# OPA847.net
KiCad netlist of a schematic drawn in Altium Designer
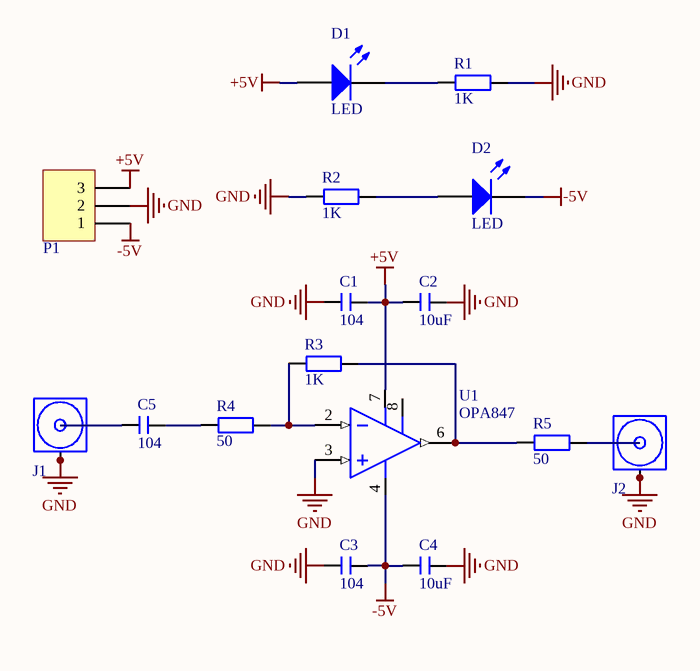
[diagram p0: OPA847.SchDoc]

(export (version "E")
  (design (tool "Eeschema 10.0.6"))
  (components
    (comp (ref "C1")
      (value "104")
      (footprint "C 0805")
      (description "无极性贴片电容")
      (fields (field (name "版权归属") "源创客"))
      (libsource (lib "电阻-电容-电感") (part "C"))
    )
    (comp (ref "C2")
      (value "10uF")
      (footprint "C 0805")
      (description "无极性贴片电容")
      (fields (field (name "版权归属") "源创客"))
      (libsource (lib "电阻-电容-电感") (part "C"))
    )
    (comp (ref "C3")
      (value "104")
      (footprint "C 0805")
      (description "无极性贴片电容")
      (fields (field (name "版权归属") "源创客"))
      (libsource (lib "电阻-电容-电感") (part "C"))
    )
    (comp (ref "C4")
      (value "10uF")
      (footprint "C 0805")
      (description "无极性贴片电容")
      (fields (field (name "版权归属") "源创客"))
      (libsource (lib "电阻-电容-电感") (part "C"))
    )
    (comp (ref "C5")
      (value "104")
      (footprint "C 0603")
      (description "无极性贴片电容")
      (fields (field (name "版权归属") "源创客"))
      (libsource (lib "电阻-电容-电感") (part "C"))
    )
    (comp (ref "D1")
      (value "LED")
      (footprint "LED_0805")
      (description "发光二极管")
      (fields (field (name "PUBLISHER") "Altium Limited"))
      (libsource (lib "LIB") (part "LED"))
    )
    (comp (ref "D2")
      (value "LED")
      (footprint "LED_0805")
      (description "发光二极管")
      (fields (field (name "PUBLISHER") "Altium Limited"))
      (libsource (lib "LIB") (part "LED"))
    )
    (comp (ref "J1") (value "COAX") (footprint "MCX5.08-5-H") (libsource (lib "LIB") (part "COAX")))
    (comp (ref "J2") (value "COAX") (footprint "MCX5.08-5-H") (libsource (lib "LIB") (part "COAX")))
    (comp (ref "P1")
      (value "Header 3")
      (footprint "HDR3X1_B2")
      (description "接插件")
      (fields (field (name "PUBLISHER") "Altium Limited"))
      (libsource (lib "LIB") (part "Header 3"))
    )
    (comp (ref "R1")
      (value "1K")
      (footprint "R 0805")
      (description "贴片电阻")
      (fields (field (name "版权归属") "源创客"))
      (libsource (lib "电阻-电容-电感") (part "R"))
    )
    (comp (ref "R2")
      (value "1K")
      (footprint "R 0805")
      (description "贴片电阻")
      (fields (field (name "版权归属") "源创客"))
      (libsource (lib "电阻-电容-电感") (part "R"))
    )
    (comp (ref "R3")
      (value "1K")
      (footprint "R 0603")
      (description "贴片电阻")
      (fields (field (name "版权归属") "源创客"))
      (libsource (lib "电阻-电容-电感") (part "R"))
    )
    (comp (ref "R4")
      (value "50")
      (footprint "R 0603")
      (description "贴片电阻")
      (fields (field (name "版权归属") "源创客"))
      (libsource (lib "电阻-电容-电感") (part "R"))
    )
    (comp (ref "R5")
      (value "50")
      (footprint "R 0603")
      (description "贴片电阻")
      (fields (field (name "版权归属") "源创客"))
      (libsource (lib "电阻-电容-电感") (part "R"))
    )
    (comp (ref "U1")
      (value "OPA847")
      (footprint "SO8_N")
      (description "Wideband, Ultra-Low Noise, Voltage-Feedback")
      (libsource (lib "LIB") (part "OPA847"))
    )
  )
  (nets
    (net (code "1") (name "+5V") (class "Default")
      (node (ref "C1") (pin "2") (pinfunction "2_2") (pintype "passive"))
      (node (ref "C2") (pin "1") (pinfunction "1_1") (pintype "passive"))
      (node (ref "D1") (pin "1") (pinfunction "A_1") (pintype "passive"))
      (node (ref "P1") (pin "3") (pinfunction "3_3") (pintype "passive"))
      (node (ref "U1") (pin "7") (pinfunction "V+_7") (pintype "power_in"))
    )
    (net (code "2") (name "-5V") (class "Default")
      (node (ref "C3") (pin "2") (pinfunction "2_2") (pintype "passive"))
      (node (ref "C4") (pin "1") (pinfunction "1_1") (pintype "passive"))
      (node (ref "D2") (pin "2") (pinfunction "K_2") (pintype "passive"))
      (node (ref "P1") (pin "1") (pinfunction "1_1") (pintype "passive"))
      (node (ref "U1") (pin "4") (pinfunction "V-_4") (pintype "power_in"))
    )
    (net (code "3") (name "GND") (class "Default")
      (node (ref "C1") (pin "1") (pinfunction "1_1") (pintype "passive"))
      (node (ref "C2") (pin "2") (pinfunction "2_2") (pintype "passive"))
      (node (ref "C3") (pin "1") (pinfunction "1_1") (pintype "passive"))
      (node (ref "C4") (pin "2") (pinfunction "2_2") (pintype "passive"))
      (node (ref "J1") (pin "2") (pinfunction "GND_2") (pintype "passive"))
      (node (ref "J1") (pin "3") (pinfunction "GND_3") (pintype "passive"))
      (node (ref "J1") (pin "4") (pinfunction "GND_4") (pintype "passive"))
      (node (ref "J1") (pin "5") (pinfunction "GND_5") (pintype "passive"))
      (node (ref "J2") (pin "2") (pinfunction "GND_2") (pintype "passive"))
      (node (ref "J2") (pin "3") (pinfunction "GND_3") (pintype "passive"))
      (node (ref "J2") (pin "4") (pinfunction "GND_4") (pintype "passive"))
      (node (ref "J2") (pin "5") (pinfunction "GND_5") (pintype "passive"))
      (node (ref "P1") (pin "2") (pinfunction "2_2") (pintype "passive"))
      (node (ref "R1") (pin "2") (pinfunction "2_2") (pintype "passive"))
      (node (ref "R2") (pin "1") (pinfunction "1_1") (pintype "passive"))
      (node (ref "U1") (pin "3") (pinfunction "IN+_3") (pintype "input"))
    )
    (net (code "4") (name "Net-(C5-Pad2)") (class "Default")
      (node (ref "C5") (pin "2") (pinfunction "2_2") (pintype "passive"))
      (node (ref "R4") (pin "1") (pinfunction "1_1") (pintype "passive"))
    )
    (net (code "5") (name "Net-(D1-K)") (class "Default")
      (node (ref "D1") (pin "2") (pinfunction "K_2") (pintype "passive"))
      (node (ref "R1") (pin "1") (pinfunction "1_1") (pintype "passive"))
    )
    (net (code "6") (name "Net-(D2-A)") (class "Default")
      (node (ref "D2") (pin "1") (pinfunction "A_1") (pintype "passive"))
      (node (ref "R2") (pin "2") (pinfunction "2_2") (pintype "passive"))
    )
    (net (code "7") (name "Net-(J1-Signal)") (class "Default")
      (node (ref "C5") (pin "1") (pinfunction "1_1") (pintype "passive"))
      (node (ref "J1") (pin "1") (pinfunction "Signal_1") (pintype "passive"))
    )
    (net (code "8") (name "Net-(J2-Signal)") (class "Default")
      (node (ref "J2") (pin "1") (pinfunction "Signal_1") (pintype "passive"))
      (node (ref "R5") (pin "2") (pinfunction "2_2") (pintype "passive"))
    )
    (net (code "9") (name "Net-(U1-IN-)") (class "Default")
      (node (ref "R3") (pin "1") (pinfunction "1_1") (pintype "passive"))
      (node (ref "R4") (pin "2") (pinfunction "2_2") (pintype "passive"))
      (node (ref "U1") (pin "2") (pinfunction "IN-_2") (pintype "input"))
    )
    (net (code "10") (name "Net-(U1-OUT)") (class "Default")
      (node (ref "R3") (pin "2") (pinfunction "2_2") (pintype "passive"))
      (node (ref "R5") (pin "1") (pinfunction "1_1") (pintype "passive"))
      (node (ref "U1") (pin "6") (pinfunction "OUT_6") (pintype "output"))
    )
    (net (code "11") (name "unconnected-(U1-Pad8)") (class "Default")
      (node (ref "U1") (pin "8") (pinfunction "8_8") (pintype "passive"))
    )
  )
)
